# X_line_07.net
KiCad netlist of a schematic drawn in Altium Designer
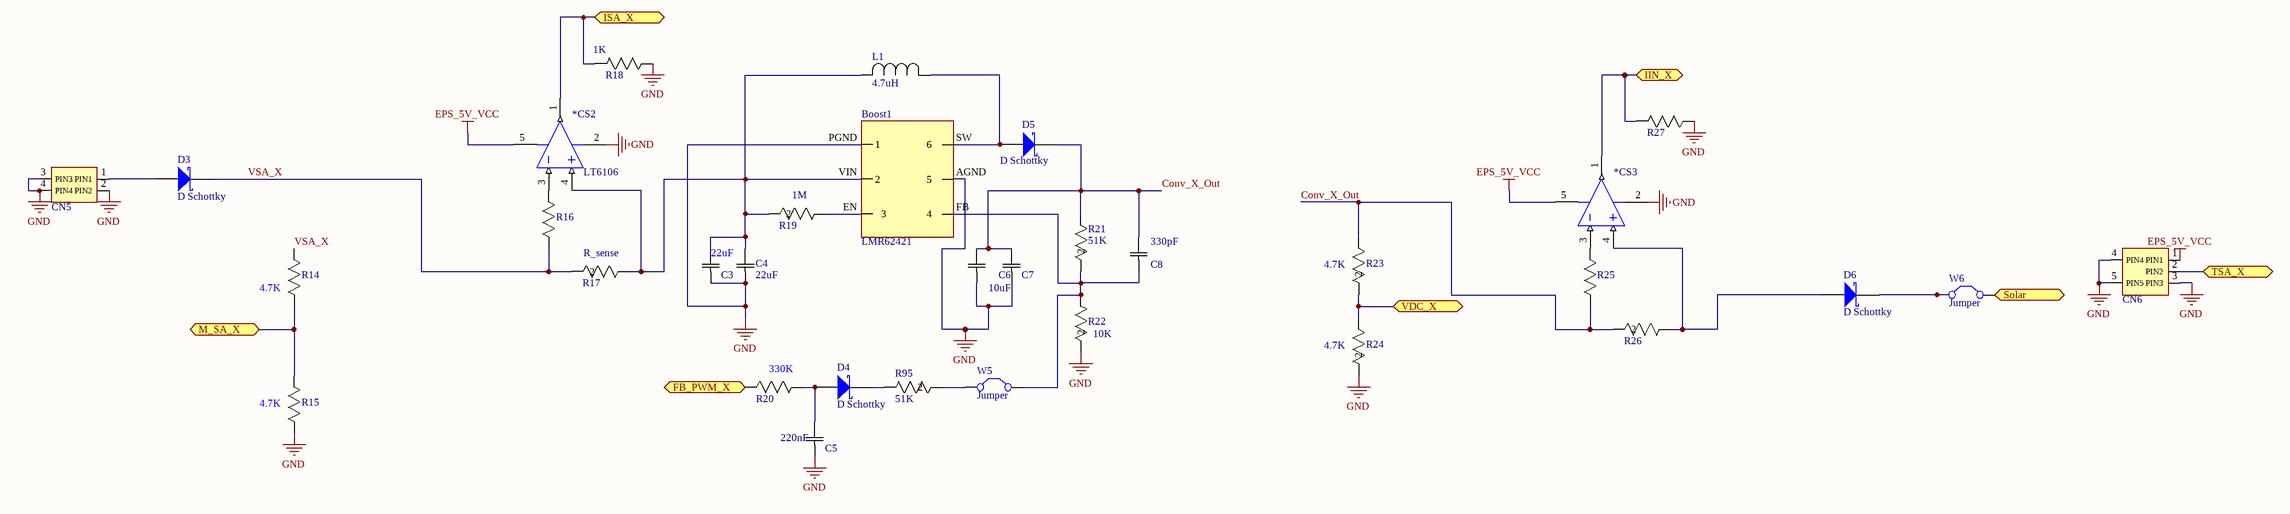
[diagram p0: X_line_07.SchDoc]

(export (version "E")
  (design (tool "Eeschema 10.0.6"))
  (components
    (comp (ref "*CS2")
      (value "LT6106")
      (footprint "LT-S5-5-TSOT-23_N")
      (fields
        (field (name "MANUFACTURER") "Linear Technology")
        (field (name "PARTNUMBER") "LT6106HS5#TRMPBF")
      )
      (libsource (lib "Linear Technology Operational Amplifiers (LT2000-LT6000)") (part "LT6106HS5#TRMPBF"))
    )
    (comp (ref "*CS3")
      (value "CS3")
      (footprint "LT-S5-5-TSOT-23_N")
      (fields
        (field (name "LINEAR TECHNOLOGY PART NUMBER") "LT6106")
        (field (name "MANUFACTURER") "Linear Technology")
        (field (name "PARTNUMBER") "LT6106HS5#TRMPBF")
      )
      (libsource (lib "Linear Technology Operational Amplifiers (LT2000-LT6000)") (part "LT6106HS5#TRMPBF"))
    )
    (comp (ref "Boost1")
      (value "LMR62421")
      (footprint "PcbLib_2:LMR62421")
      (description "LMR62421XSDDEMO: 12V @ 500mA, 2.7 ~ 5.5V in")
      (libsource (lib "LMR62421_2") (part "Component_1"))
    )
    (comp (ref "C3")
      (value "22uF")
      (footprint "RC0805N")
      (description "Ceramic Capacitor 0402")
      (fields
        (field (name "MANUFACTURER_PART_NUMBER") "GRM155R71H103KA88D")
        (field (name "Comment") "GRM155R71H103KA8")
        (field (name "COPYRIGHT") "Copyright (C) 2015 Accelerated Designs. All rights reserved")
      )
      (libsource (lib "Schlib1") (part "GRM155R71H103KA8"))
    )
    (comp (ref "C4")
      (value "22uF")
      (footprint "RC0805N")
      (description "Ceramic Capacitor")
      (fields
        (field (name "MANUFACTURER_PART_NUMBER") "GRM155R71H103KA88D")
        (field (name "COPYRIGHT") "Copyright (C) 2015 Accelerated Designs. All rights reserved")
      )
      (libsource (lib "PCDU_Library") (part "GRM155R71H103KA8"))
    )
    (comp (ref "C5")
      (value "220nF")
      (footprint "RC0805N")
      (description "Ceramic Capacitor 47uF 0603")
      (fields
        (field (name "MANUFACTURER_PART_NUMBER") "GRM188R71H472KA01D")
        (field (name "COPYRIGHT") "Copyright (C) 2015 Accelerated Designs. All rights reserved")
      )
      (libsource (lib "Schlib1") (part "GRM188R71H472KA0"))
    )
    (comp (ref "C6")
      (value "10uF")
      (footprint "RC0805N")
      (description "Ceramic Capacitor 47uF 0603")
      (fields
        (field (name "MANUFACTURER_PART_NUMBER") "GRM188R71H472KA01D")
        (field (name "COPYRIGHT") "Copyright (C) 2015 Accelerated Designs. All rights reserved")
      )
      (libsource (lib "PCDU_Library") (part "GRM188R71H472KA0"))
    )
    (comp (ref "C7")
      (value "GRM155R71H103KA8")
      (footprint "RC0805N")
      (description "Ceramic Capacitor 0402")
      (fields
        (field (name "MANUFACTURER_PART_NUMBER") "GRM155R71H103KA88D")
        (field (name "COPYRIGHT") "Copyright (C) 2015 Accelerated Designs. All rights reserved")
      )
      (libsource (lib "Schlib1") (part "GRM155R71H103KA8"))
    )
    (comp (ref "C8")
      (value "330pF")
      (footprint "RC0805N")
      (description "Ceramic Capacitor")
      (fields
        (field (name "MANUFACTURER_PART_NUMBER") "GRM155R71H103KA88D")
        (field (name "COPYRIGHT") "Copyright (C) 2015 Accelerated Designs. All rights reserved")
      )
      (libsource (lib "PCDU_Library") (part "GRM155R71H103KA8"))
    )
    (comp (ref "CN5")
      (value "SM02B-SRSS")
      (footprint "2pins")
      (description "CONN HEADER SH 2POS SIDE 1MM TIN")
      (fields
        (field (name "DIGI-KEY PART NUMBER") "455-1802-1-ND")
        (field (name "MANUFACTURER PART NUMBER") "SM02B-SRSS-TB(LF)(SN)")
      )
      (libsource (lib "EPS_lib") (part "2Pin_Connector"))
    )
    (comp (ref "CN6")
      (value "SM03B-SRSS")
      (footprint "3pins")
      (description "CONN HEADER SH 3POS SIDE 1MM TIN")
      (fields
        (field (name "DIGI-KEY PART NUMBER") "455-1803-1-ND")
        (field (name "MANUFACTURER PART NUMBER") "SM03B-SRSS-TB(LF)(SN)")
      )
      (libsource (lib "EPS_lib") (part "3PIN_Connector"))
    )
    (comp (ref "D3")
      (value "D Schottky")
      (footprint "trial05:SMB")
      (description "Schottky Diode, 1A")
      (fields (field (name "PUBLISHER") "Altium Limited"))
      (libsource (lib "PCDU_Library") (part "D Schottky"))
    )
    (comp (ref "D4")
      (value "D Schottky")
      (footprint "SMB")
      (description "Schottky Diode, 1A")
      (fields (field (name "PUBLISHER") "Altium Limited"))
      (libsource (lib "Schlib1") (part "D Schottky"))
    )
    (comp (ref "D5")
      (value "D Schottky")
      (footprint "SMB")
      (description "Schottky Diode, 1A")
      (fields (field (name "PUBLISHER") "Altium Limited"))
      (libsource (lib "PCDU_Library") (part "D Schottky"))
    )
    (comp (ref "D6")
      (value "D Schottky")
      (footprint "SMB")
      (description "Schottky Diode, 1A")
      (fields (field (name "PUBLISHER") "Altium Limited"))
      (libsource (lib "PCDU_Library") (part "D Schottky"))
    )
    (comp (ref "L1")
      (value "4.7uH")
      (footprint "IND_SPM6530")
      (description "Inductor, 4.7uH")
      (fields
        (field (name "MANUFACTURER_PART_NUMBER") "SPM6530T-4R7M")
        (field (name "COPYRIGHT") "Copyright (C) 2015 Accelerated Designs. All rights reserved")
      )
      (libsource (lib "PCDU_Library") (part "SPM6530T-4R7M"))
    )
    (comp (ref "R14")
      (value "RC0805FR")
      (footprint "RC0805N")
      (description "Thick Film Resistors 0805")
      (fields
        (field (name "DIGIKEYPARTNUMBER") "311-4.70KCRTR-ND")
        (field (name "MANUFACTURER_PART_NUMBER") "RC0805FR-074K7L")
        (field (name "RESISTANCE_(OHMS)") "4.7K")
        (field (name "COPYRIGHT") "Copyright (C) 2015 Accelerated Designs. All rights reserved")
      )
      (libsource (lib "Schlib1") (part "RC0805FR"))
    )
    (comp (ref "R15")
      (value "RC0805FR")
      (footprint "RC0805N")
      (description "Thick Film Resistors 0805")
      (fields
        (field (name "DIGIKEYPARTNUMBER") "311-4.70KCRTR-ND")
        (field (name "MANUFACTURER_PART_NUMBER") "RC0805FR-074K7L")
        (field (name "RESISTANCE_(OHMS)") "4.7K")
        (field (name "COPYRIGHT") "Copyright (C) 2015 Accelerated Designs. All rights reserved")
      )
      (libsource (lib "Schlib1") (part "RC0805FR"))
    )
    (comp (ref "R16")
      (value "1K")
      (footprint "RC0805N")
      (description "Thick Film Resistors 0805")
      (fields
        (field (name "DIGIKEYPARTNUMBER") "311-4.70KCRTR-ND")
        (field (name "MANUFACTURER_PART_NUMBER") "RC0805FR-074K7L")
        (field (name "COPYRIGHT") "Copyright (C) 2015 Accelerated Designs. All rights reserved")
      )
      (libsource (lib "Schlib1") (part "RC0805FR"))
    )
    (comp (ref "R17")
      (value "R_sense")
      (footprint "RC0805N")
      (description "Sense Resistor 100m ohm 0805")
      (fields
        (field (name "DIGIKEYPARTNUMBER") "311-.10STR-ND")
        (field (name "MANUFACTURER_PART_NUMBER") "RL0805FR-070R1L")
        (field (name "COPYRIGHT") "Copyright (C) 2015 Accelerated Designs. All rights reserved")
      )
      (libsource (lib "Schlib1") (part "RL0805FR-070R1L"))
    )
    (comp (ref "R18")
      (value "1K")
      (footprint "RC0805N")
      (description "Thick Film Resistors 0805")
      (fields
        (field (name "DIGIKEYPARTNUMBER") "311-4.70KCRTR-ND")
        (field (name "MANUFACTURER_PART_NUMBER") "RC0805FR-074K7L")
        (field (name "COPYRIGHT") "Copyright (C) 2015 Accelerated Designs. All rights reserved")
      )
      (libsource (lib "Schlib1") (part "RC0805FR"))
    )
    (comp (ref "R19")
      (value "1M")
      (footprint "RC0805N")
      (description "Thick Film Resistors 0805")
      (fields
        (field (name "DIGIKEYPARTNUMBER") "311-4.70KCRTR-ND")
        (field (name "MANUFACTURER_PART_NUMBER") "RC0805FR-074K7L")
        (field (name "COPYRIGHT") "Copyright (C) 2015 Accelerated Designs. All rights reserved")
      )
      (libsource (lib "PCDU_Library") (part "RC0805FR"))
    )
    (comp (ref "R20")
      (value "RC0805FR")
      (footprint "RC0805N")
      (description "Thick Film Resistors 0805")
      (fields
        (field (name "DIGIKEYPARTNUMBER") "311-4.70KCRTR-ND")
        (field (name "MANUFACTURER_PART_NUMBER") "RC0805FR-074K7L")
        (field (name "RESISTANCE_(OHMS)") "330K")
        (field (name "COPYRIGHT") "Copyright (C) 2015 Accelerated Designs. All rights reserved")
      )
      (libsource (lib "Schlib1") (part "RC0805FR"))
    )
    (comp (ref "R21")
      (value "51K")
      (footprint "RC0805N")
      (description "Thick Film Resistors 0805")
      (fields
        (field (name "DIGIKEYPARTNUMBER") "311-4.70KCRTR-ND")
        (field (name "MANUFACTURER_PART_NUMBER") "RC0805FR-074K7L")
        (field (name "COPYRIGHT") "Copyright (C) 2015 Accelerated Designs. All rights reserved")
      )
      (libsource (lib "PCDU_Library") (part "RC0805FR"))
    )
    (comp (ref "R22")
      (value "10K")
      (footprint "RC0805N")
      (description "Thick Film Resistors 0805")
      (fields
        (field (name "DIGIKEYPARTNUMBER") "311-4.70KCRTR-ND")
        (field (name "MANUFACTURER_PART_NUMBER") "RC0805FR-074K7L")
        (field (name "COPYRIGHT") "Copyright (C) 2015 Accelerated Designs. All rights reserved")
      )
      (libsource (lib "PCDU_Library") (part "RC0805FR"))
    )
    (comp (ref "R23")
      (value "4.7K")
      (footprint "RC0805N")
      (description "Thick Film Resistors 0805")
      (fields
        (field (name "DIGIKEYPARTNUMBER") "311-4.70KCRTR-ND")
        (field (name "MANUFACTURER_PART_NUMBER") "RC0805FR-074K7L")
        (field (name "COPYRIGHT") "Copyright (C) 2015 Accelerated Designs. All rights reserved")
      )
      (libsource (lib "PCDU_Library") (part "RC0805FR"))
    )
    (comp (ref "R24")
      (value "4.7K")
      (footprint "RC0805N")
      (description "Thick Film Resistors 0805")
      (fields
        (field (name "DIGIKEYPARTNUMBER") "311-4.70KCRTR-ND")
        (field (name "MANUFACTURER_PART_NUMBER") "RC0805FR-074K7L")
        (field (name "COPYRIGHT") "Copyright (C) 2015 Accelerated Designs. All rights reserved")
      )
      (libsource (lib "PCDU_Library") (part "RC0805FR"))
    )
    (comp (ref "R25")
      (value "RC0805FR")
      (footprint "RC0805N")
      (description "Thick Film Resistors 0805")
      (fields
        (field (name "DIGIKEYPARTNUMBER") "311-4.70KCRTR-ND")
        (field (name "MANUFACTURER_PART_NUMBER") "RC0805FR-074K7L")
        (field (name "COPYRIGHT") "Copyright (C) 2015 Accelerated Designs. All rights reserved")
      )
      (libsource (lib "Schlib1") (part "RC0805FR"))
    )
    (comp (ref "R26")
      (value "RL0805FR-070R1L")
      (footprint "RC0805N")
      (description "Sense Resistor 100m ohm 0805")
      (fields
        (field (name "DIGIKEYPARTNUMBER") "311-.10STR-ND")
        (field (name "TOLERANCE") "Â±1%")
        (field (name "COPYRIGHT") "Copyright (C) 2015 Accelerated Designs. All rights reserved")
      )
      (libsource (lib "Schlib1") (part "RL0805FR-070R1L"))
    )
    (comp (ref "R27")
      (value "RC0805FR")
      (footprint "RC0805N")
      (description "Thick Film Resistors 0805")
      (fields
        (field (name "DIGIKEYPARTNUMBER") "311-4.70KCRTR-ND")
        (field (name "MANUFACTURER_PART_NUMBER") "RC0805FR-074K7L")
        (field (name "COPYRIGHT") "Copyright (C) 2015 Accelerated Designs. All rights reserved")
      )
      (libsource (lib "Schlib1") (part "RC0805FR"))
    )
    (comp (ref "R95")
      (value "51K")
      (footprint "RC0805N")
      (description "Thick Film Resistors 0805")
      (fields
        (field (name "DIGIKEYPARTNUMBER") "311-4.70KCRTR-ND")
        (field (name "MANUFACTURER_PART_NUMBER") "RC0805FR-074K7L")
        (field (name "COPYRIGHT") "Copyright (C) 2015 Accelerated Designs. All rights reserved")
      )
      (libsource (lib "PCDU_Library") (part "RC0805FR"))
    )
    (comp (ref "W5")
      (value "Jumper")
      (footprint "PcbLib1:RAD-0.1")
      (description "Jumper Wire")
      (fields (field (name "PUBLISHER") "Altium Limited"))
      (libsource (lib "PCDU_Library") (part "Jumper"))
    )
    (comp (ref "W6")
      (value "Jumper")
      (footprint "PcbLib1:RAD-0.1")
      (description "Jumper Wire")
      (fields (field (name "PUBLISHER") "Altium Limited"))
      (libsource (lib "PCDU_Library") (part "Jumper"))
    )
  )
  (nets
    (net (code "1") (name "/Conv_X_Out") (class "Default")
      (node (ref "C6") (pin "2") (pinfunction "2_2") (pintype "passive"))
      (node (ref "C7") (pin "2") (pinfunction "2_2") (pintype "passive"))
      (node (ref "C8") (pin "2") (pinfunction "2_2") (pintype "passive"))
      (node (ref "D5") (pin "2") (pinfunction "K_2") (pintype "passive"))
      (node (ref "R21") (pin "1") (pinfunction "1_1") (pintype "passive"))
      (node (ref "R23") (pin "1") (pinfunction "1_1") (pintype "passive"))
      (node (ref "R25") (pin "2") (pinfunction "2_2") (pintype "passive"))
      (node (ref "R26") (pin "2") (pinfunction "2_2") (pintype "passive"))
    )
    (net (code "2") (name "/FB_PWM_X") (class "Default")
      (node (ref "R20") (pin "2") (pinfunction "2_2") (pintype "passive"))
    )
    (net (code "3") (name "/IIN_X") (class "Default")
      (node (ref "*CS3") (pin "1") (pinfunction "OUT_1") (pintype "output"))
      (node (ref "R27") (pin "1") (pinfunction "1_1") (pintype "passive"))
    )
    (net (code "4") (name "/ISA_X") (class "Default")
      (node (ref "*CS2") (pin "1") (pinfunction "OUT_1") (pintype "output"))
      (node (ref "R18") (pin "1") (pinfunction "1_1") (pintype "passive"))
    )
    (net (code "5") (name "/M_SA_X") (class "Default")
      (node (ref "R14") (pin "2") (pinfunction "2_2") (pintype "passive"))
      (node (ref "R15") (pin "1") (pinfunction "1_1") (pintype "passive"))
    )
    (net (code "6") (name "/Solar") (class "Default")
      (node (ref "W6") (pin "2") (pinfunction "C2_2") (pintype "passive"))
    )
    (net (code "7") (name "/TSA_X") (class "Default")
      (node (ref "CN6") (pin "2") (pinfunction "PIN2_2") (pintype "passive"))
    )
    (net (code "8") (name "/VDC_X") (class "Default")
      (node (ref "R23") (pin "2") (pinfunction "2_2") (pintype "passive"))
      (node (ref "R24") (pin "1") (pinfunction "1_1") (pintype "passive"))
    )
    (net (code "9") (name "/VSA_X") (class "Default")
      (node (ref "D3") (pin "2") (pinfunction "K_2") (pintype "passive"))
      (node (ref "R14") (pin "1") (pinfunction "1_1") (pintype "passive"))
      (node (ref "R16") (pin "2") (pinfunction "2_2") (pintype "passive"))
      (node (ref "R17") (pin "2") (pinfunction "2_2") (pintype "passive"))
    )
    (net (code "10") (name "EPS_5V_VCC") (class "Default")
      (node (ref "*CS2") (pin "5") (pinfunction "V+_5") (pintype "power_in"))
      (node (ref "*CS3") (pin "5") (pinfunction "V+_5") (pintype "power_in"))
      (node (ref "CN6") (pin "1") (pinfunction "PIN1_1") (pintype "passive"))
    )
    (net (code "11") (name "GND") (class "Default")
      (node (ref "*CS2") (pin "2") (pinfunction "V-_2") (pintype "power_in"))
      (node (ref "*CS3") (pin "2") (pinfunction "V-_2") (pintype "power_in"))
      (node (ref "Boost1") (pin "AGND") (pinfunction "5_AGND") (pintype "passive"))
      (node (ref "Boost1") (pin "PGND") (pinfunction "1_PGND") (pintype "passive"))
      (node (ref "C3") (pin "1") (pinfunction "1_1") (pintype "passive"))
      (node (ref "C4") (pin "1") (pinfunction "1_1") (pintype "passive"))
      (node (ref "C5") (pin "1") (pinfunction "1_1") (pintype "passive"))
      (node (ref "C6") (pin "1") (pinfunction "1_1") (pintype "passive"))
      (node (ref "C7") (pin "1") (pinfunction "1_1") (pintype "passive"))
      (node (ref "CN5") (pin "2") (pinfunction "PIN2_2") (pintype "passive"))
      (node (ref "CN5") (pin "3") (pinfunction "PIN3_3") (pintype "passive"))
      (node (ref "CN5") (pin "4") (pinfunction "PIN4_4") (pintype "passive"))
      (node (ref "CN6") (pin "3") (pinfunction "PIN3_3") (pintype "passive"))
      (node (ref "CN6") (pin "4") (pinfunction "PIN4_4") (pintype "passive"))
      (node (ref "CN6") (pin "5") (pinfunction "PIN5_5") (pintype "passive"))
      (node (ref "R15") (pin "2") (pinfunction "2_2") (pintype "passive"))
      (node (ref "R18") (pin "2") (pinfunction "2_2") (pintype "passive"))
      (node (ref "R22") (pin "2") (pinfunction "2_2") (pintype "passive"))
      (node (ref "R24") (pin "2") (pinfunction "2_2") (pintype "passive"))
      (node (ref "R27") (pin "2") (pinfunction "2_2") (pintype "passive"))
    )
    (net (code "12") (name "Net-(*CS2-+IN)") (class "Default")
      (node (ref "*CS2") (pin "4") (pinfunction "+IN_4") (pintype "input"))
      (node (ref "Boost1") (pin "VIN") (pinfunction "2_VIN") (pintype "passive"))
      (node (ref "C3") (pin "2") (pinfunction "2_2") (pintype "passive"))
      (node (ref "C4") (pin "2") (pinfunction "2_2") (pintype "passive"))
      (node (ref "L1") (pin "2") (pinfunction "2_2") (pintype "passive"))
      (node (ref "R17") (pin "1") (pinfunction "1_1") (pintype "passive"))
      (node (ref "R19") (pin "2") (pinfunction "2_2") (pintype "passive"))
    )
    (net (code "13") (name "Net-(*CS2--IN)") (class "Default")
      (node (ref "*CS2") (pin "3") (pinfunction "-IN_3") (pintype "input"))
      (node (ref "R16") (pin "1") (pinfunction "1_1") (pintype "passive"))
    )
    (net (code "14") (name "Net-(*CS3-+IN)") (class "Default")
      (node (ref "*CS3") (pin "4") (pinfunction "+IN_4") (pintype "input"))
      (node (ref "D6") (pin "1") (pinfunction "A_1") (pintype "passive"))
      (node (ref "R26") (pin "1") (pinfunction "1_1") (pintype "passive"))
    )
    (net (code "15") (name "Net-(*CS3--IN)") (class "Default")
      (node (ref "*CS3") (pin "3") (pinfunction "-IN_3") (pintype "input"))
      (node (ref "R25") (pin "1") (pinfunction "1_1") (pintype "passive"))
    )
    (net (code "16") (name "Net-(Boost1-3)") (class "Default")
      (node (ref "Boost1") (pin "EN") (pinfunction "3_EN") (pintype "passive"))
      (node (ref "R19") (pin "1") (pinfunction "1_1") (pintype "passive"))
    )
    (net (code "17") (name "Net-(Boost1-4)") (class "Default")
      (node (ref "Boost1") (pin "FB") (pinfunction "4_FB") (pintype "passive"))
      (node (ref "C8") (pin "1") (pinfunction "1_1") (pintype "passive"))
      (node (ref "R21") (pin "2") (pinfunction "2_2") (pintype "passive"))
      (node (ref "R22") (pin "1") (pinfunction "1_1") (pintype "passive"))
      (node (ref "W5") (pin "2") (pinfunction "C2_2") (pintype "passive"))
    )
    (net (code "18") (name "Net-(Boost1-6)") (class "Default")
      (node (ref "Boost1") (pin "SW") (pinfunction "6_SW") (pintype "passive"))
      (node (ref "D5") (pin "1") (pinfunction "A_1") (pintype "passive"))
      (node (ref "L1") (pin "1") (pinfunction "1_1") (pintype "passive"))
    )
    (net (code "19") (name "Net-(CN5-PIN1)") (class "Default")
      (node (ref "CN5") (pin "1") (pinfunction "PIN1_1") (pintype "passive"))
      (node (ref "D3") (pin "1") (pinfunction "A_1") (pintype "passive"))
    )
    (net (code "20") (name "Net-(D4-A)") (class "Default")
      (node (ref "C5") (pin "2") (pinfunction "2_2") (pintype "passive"))
      (node (ref "D4") (pin "1") (pinfunction "A_1") (pintype "passive"))
      (node (ref "R20") (pin "1") (pinfunction "1_1") (pintype "passive"))
    )
    (net (code "21") (name "Net-(D4-K)") (class "Default")
      (node (ref "D4") (pin "2") (pinfunction "K_2") (pintype "passive"))
      (node (ref "R95") (pin "1") (pinfunction "1_1") (pintype "passive"))
    )
    (net (code "22") (name "Net-(D6-K)") (class "Default")
      (node (ref "D6") (pin "2") (pinfunction "K_2") (pintype "passive"))
      (node (ref "W6") (pin "1") (pinfunction "C1_1") (pintype "passive"))
    )
    (net (code "23") (name "Net-(W5-C1)") (class "Default")
      (node (ref "R95") (pin "2") (pinfunction "2_2") (pintype "passive"))
      (node (ref "W5") (pin "1") (pinfunction "C1_1") (pintype "passive"))
    )
  )
)
